# ts19390-boost-24mm-9leds-mk-1.net
KiCad netlist of a schematic drawn in EAGLE
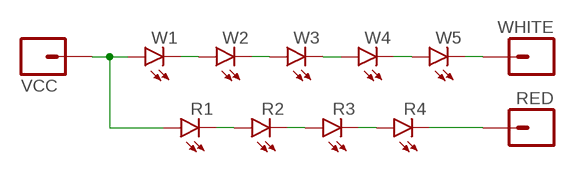
[diagram p0: schematic, sheet 1]

(export (version "E")
  (design (tool "Eeschema 10.0.6"))
  (components
    (comp (ref "R1")
      (value "LED5MM_SHORTPADS")
      (footprint "eagle-import:LED5MM_SHORTPADS")
      (libsource (lib "eagle-import") (part "LED5MM_SHORTPADS"))
    )
    (comp (ref "R2")
      (value "LED5MM_SHORTPADS")
      (footprint "eagle-import:LED5MM_SHORTPADS")
      (libsource (lib "eagle-import") (part "LED5MM_SHORTPADS"))
    )
    (comp (ref "R3")
      (value "LED5MM_SHORTPADS")
      (footprint "eagle-import:LED5MM_SHORTPADS")
      (libsource (lib "eagle-import") (part "LED5MM_SHORTPADS"))
    )
    (comp (ref "R4")
      (value "LED5MM_SHORTPADS")
      (footprint "eagle-import:LED5MM_SHORTPADS")
      (libsource (lib "eagle-import") (part "LED5MM_SHORTPADS"))
    )
    (comp (ref "RED")
      (value "M01PTH-NS-NOTSUCK")
      (footprint "eagle-import:1X01NSATALL")
      (libsource (lib "eagle-import") (part "M01PTH-NS-NOTSUCK"))
    )
    (comp (ref "VCC")
      (value "M01PTH-NS-NOTSUCK")
      (footprint "eagle-import:1X01NSATALL")
      (libsource (lib "eagle-import") (part "M01PTH-NS-NOTSUCK"))
    )
    (comp (ref "W1")
      (value "LED5MM_SHORTPADS")
      (footprint "eagle-import:LED5MM_SHORTPADS")
      (libsource (lib "eagle-import") (part "LED5MM_SHORTPADS"))
    )
    (comp (ref "W2")
      (value "LED5MM_SHORTPADS")
      (footprint "eagle-import:LED5MM_SHORTPADS")
      (libsource (lib "eagle-import") (part "LED5MM_SHORTPADS"))
    )
    (comp (ref "W3")
      (value "LED5MM_SHORTPADS")
      (footprint "eagle-import:LED5MM_SHORTPADS")
      (libsource (lib "eagle-import") (part "LED5MM_SHORTPADS"))
    )
    (comp (ref "W4")
      (value "LED5MM_SHORTPADS")
      (footprint "eagle-import:LED5MM_SHORTPADS")
      (libsource (lib "eagle-import") (part "LED5MM_SHORTPADS"))
    )
    (comp (ref "W5")
      (value "LED5MM_SHORTPADS")
      (footprint "eagle-import:LED5MM_SHORTPADS")
      (libsource (lib "eagle-import") (part "LED5MM_SHORTPADS"))
    )
    (comp (ref "WHITE")
      (value "M01PTH-NS-NOTSUCK")
      (footprint "eagle-import:1X01NSATALL")
      (libsource (lib "eagle-import") (part "M01PTH-NS-NOTSUCK"))
    )
  )
  (nets
    (net (code "1") (name "Net-(R1-C)") (class "Default")
      (node (ref "R1") (pin "K") (pinfunction "C_K") (pintype "passive"))
      (node (ref "R2") (pin "A") (pinfunction "A_A") (pintype "passive"))
    )
    (net (code "2") (name "Net-(R1-PadA)") (class "Default")
      (node (ref "R1") (pin "A") (pinfunction "A_A") (pintype "passive"))
      (node (ref "VCC") (pin "1") (pinfunction "1_1") (pintype "passive"))
      (node (ref "W1") (pin "A") (pinfunction "A_A") (pintype "passive"))
    )
    (net (code "3") (name "Net-(R2-C)") (class "Default")
      (node (ref "R2") (pin "K") (pinfunction "C_K") (pintype "passive"))
      (node (ref "R3") (pin "A") (pinfunction "A_A") (pintype "passive"))
    )
    (net (code "4") (name "Net-(R3-C)") (class "Default")
      (node (ref "R3") (pin "K") (pinfunction "C_K") (pintype "passive"))
      (node (ref "R4") (pin "A") (pinfunction "A_A") (pintype "passive"))
    )
    (net (code "5") (name "Net-(R4-C)") (class "Default")
      (node (ref "R4") (pin "K") (pinfunction "C_K") (pintype "passive"))
      (node (ref "RED") (pin "1") (pinfunction "1_1") (pintype "passive"))
    )
    (net (code "6") (name "Net-(W1-C)") (class "Default")
      (node (ref "W1") (pin "K") (pinfunction "C_K") (pintype "passive"))
      (node (ref "W2") (pin "A") (pinfunction "A_A") (pintype "passive"))
    )
    (net (code "7") (name "Net-(W2-C)") (class "Default")
      (node (ref "W2") (pin "K") (pinfunction "C_K") (pintype "passive"))
      (node (ref "W3") (pin "A") (pinfunction "A_A") (pintype "passive"))
    )
    (net (code "8") (name "Net-(W3-C)") (class "Default")
      (node (ref "W3") (pin "K") (pinfunction "C_K") (pintype "passive"))
      (node (ref "W4") (pin "A") (pinfunction "A_A") (pintype "passive"))
    )
    (net (code "9") (name "Net-(W4-C)") (class "Default")
      (node (ref "W4") (pin "K") (pinfunction "C_K") (pintype "passive"))
      (node (ref "W5") (pin "A") (pinfunction "A_A") (pintype "passive"))
    )
    (net (code "10") (name "Net-(W5-C)") (class "Default")
      (node (ref "W5") (pin "K") (pinfunction "C_K") (pintype "passive"))
      (node (ref "WHITE") (pin "1") (pinfunction "1_1") (pintype "passive"))
    )
  )
)
